# RADIOMASTER.net
KiCad netlist of a schematic drawn in Altium Designer
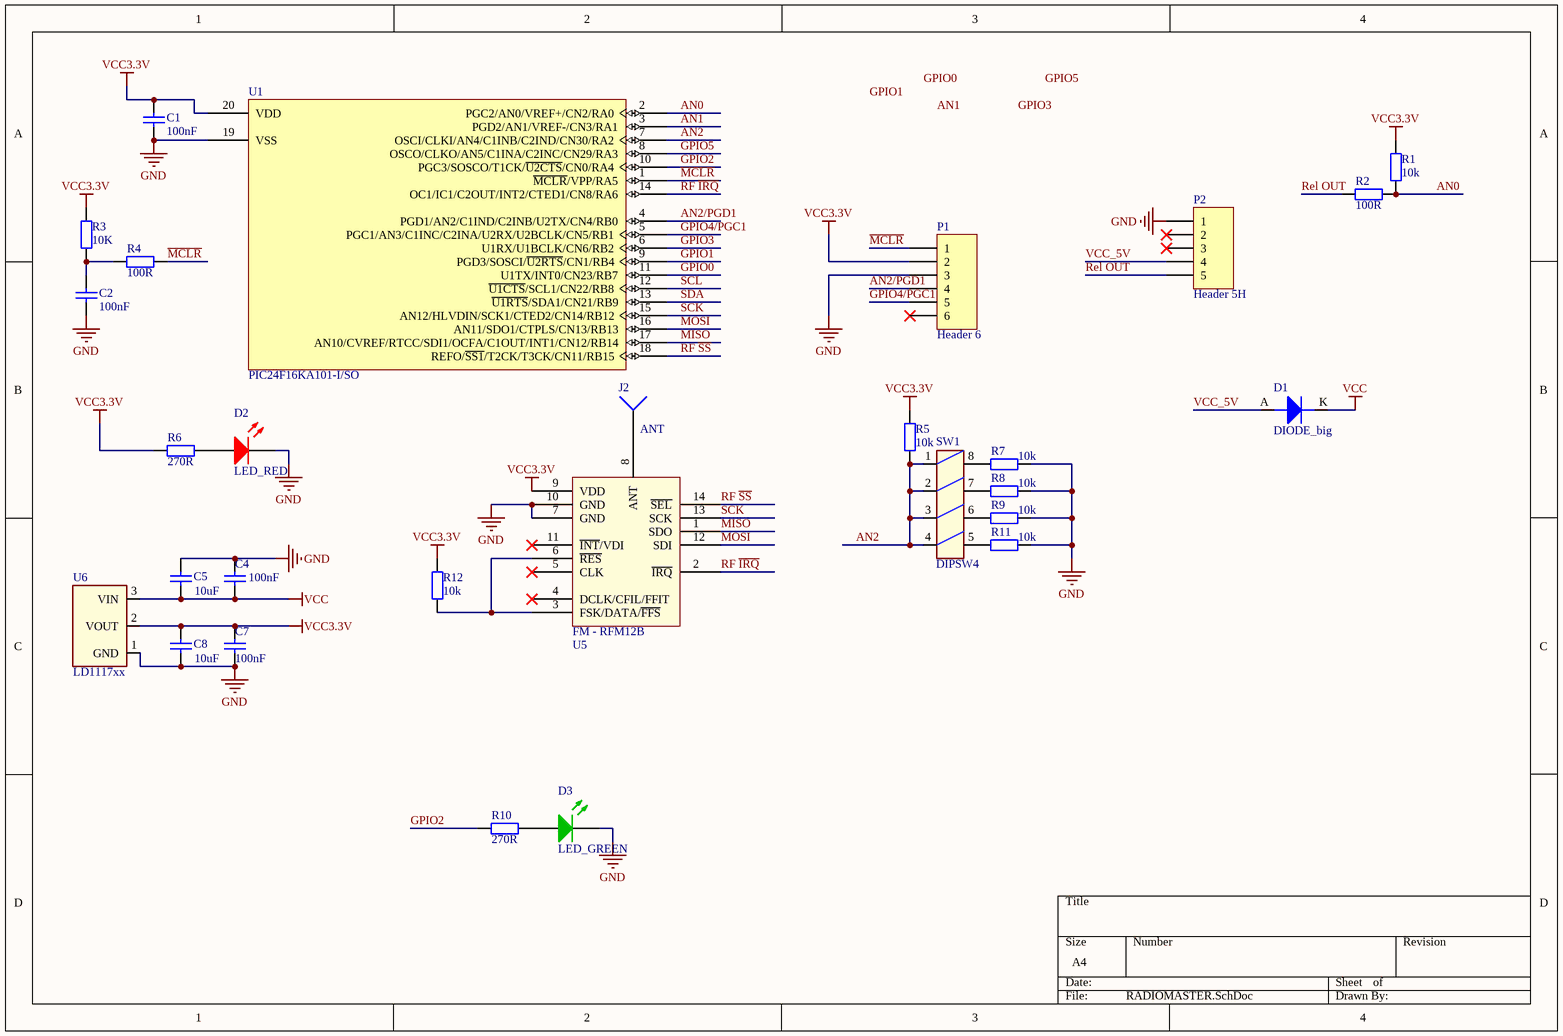
[diagram p0: RADIOMASTER.SchDoc]

(export (version "E")
  (design (tool "Eeschema 10.0.6"))
  (components
    (comp (ref "C1")
      (value "100nF")
      (footprint "FP_0805_CAP_060")
      (description "Capacitor")
      (fields (field (name "PUBLISHER") "Altium Limited"))
      (libsource (lib "Miscellaneous Devices") (part "Cap"))
    )
    (comp (ref "C2")
      (value "100nF")
      (footprint "FP_0805_CAP_060")
      (description "Capacitor")
      (fields (field (name "PUBLISHER") "Altium Limited"))
      (libsource (lib "Miscellaneous Devices") (part "Cap"))
    )
    (comp (ref "C4")
      (value "100nF")
      (footprint "FP_0603_CAP_080")
      (description "Capacitor")
      (fields (field (name "PUBLISHER") "Altium Limited"))
      (libsource (lib "Miscellaneous Devices") (part "Cap"))
    )
    (comp (ref "C5")
      (value "10uF")
      (footprint "FP_1206_CAP_085")
      (description "Capacitor")
      (fields (field (name "PUBLISHER") "Altium Limited"))
      (libsource (lib "Miscellaneous Devices") (part "Cap"))
    )
    (comp (ref "C7")
      (value "100nF")
      (footprint "FP_0603_CAP_080")
      (description "Capacitor")
      (fields (field (name "PUBLISHER") "Altium Limited"))
      (libsource (lib "Miscellaneous Devices") (part "Cap"))
    )
    (comp (ref "C8")
      (value "10uF")
      (footprint "FP_1206_CAP_085")
      (description "Capacitor")
      (fields (field (name "PUBLISHER") "Altium Limited"))
      (libsource (lib "Miscellaneous Devices") (part "Cap"))
    )
    (comp (ref "D1")
      (value "DIODE_big")
      (footprint "FP_SMA DO214AC")
      (libsource (lib "Diode") (part "DIODE_big"))
    )
    (comp (ref "D2")
      (value "LED_RED")
      (footprint "FP_0805_LED_RED")
      (description "Typical LED")
      (libsource (lib "Led_optical") (part "LED_R"))
    )
    (comp (ref "D3")
      (value "LED_GREEN")
      (footprint "FP_0805_LED_GREEN")
      (description "Typical LED")
      (libsource (lib "Led_optical") (part "LED_G"))
    )
    (comp (ref "J2")
      (value "ANT")
      (footprint "PIN1")
      (description "Socket")
      (fields (field (name "PUBLISHER") "Altium Limited"))
      (libsource (lib "Miscellaneous Connectors") (part "Socket"))
    )
    (comp (ref "P1")
      (value "Header 6")
      (footprint "HDR1X6")
      (description "Header, 6-Pin")
      (fields (field (name "PUBLISHER") "Altium Limited"))
      (libsource (lib "Miscellaneous Connectors") (part "Header 6"))
    )
    (comp (ref "P2")
      (value "Header 5H")
      (footprint "SORKAPOCS 5 P RM3.81 - no3d")
      (description "Header, 5-Pin, Right Angle")
      (fields (field (name "PUBLISHER") "Altium Limited"))
      (libsource (lib "Miscellaneous Connectors") (part "Header 5H"))
    )
    (comp (ref "R1")
      (value "10k")
      (footprint "FP_0805_RES")
      (description "Resistor")
      (fields (field (name "PUBLISHER") "Altium Limited"))
      (libsource (lib "") (part "Res3_1"))
    )
    (comp (ref "R2")
      (value "100R")
      (footprint "FP_0805_RES")
      (description "Resistor")
      (fields (field (name "PUBLISHER") "Altium Limited"))
      (libsource (lib "Miscellaneous Devices") (part "Res3"))
    )
    (comp (ref "R3")
      (value "10K")
      (footprint "FP_0805_RES")
      (description "Resistor")
      (fields (field (name "PUBLISHER") "Altium Limited"))
      (libsource (lib "") (part "Res3_1"))
    )
    (comp (ref "R4")
      (value "100R")
      (footprint "FP_0805_RES")
      (description "Resistor")
      (fields (field (name "PUBLISHER") "Altium Limited"))
      (libsource (lib "Miscellaneous Devices") (part "Res3"))
    )
    (comp (ref "R5")
      (value "10k")
      (footprint "FP_0805_RES")
      (description "Resistor")
      (fields (field (name "PUBLISHER") "Altium Limited"))
      (libsource (lib "") (part "Res3_1"))
    )
    (comp (ref "R6")
      (value "270R")
      (footprint "FP_0805_RES")
      (description "Resistor")
      (fields (field (name "PUBLISHER") "Altium Limited"))
      (libsource (lib "Miscellaneous Devices") (part "Res3"))
    )
    (comp (ref "R7")
      (value "10k")
      (footprint "FP_0805_RES")
      (description "Resistor")
      (fields (field (name "PUBLISHER") "Altium Limited"))
      (libsource (lib "Miscellaneous Devices") (part "Res3"))
    )
    (comp (ref "R8")
      (value "10k")
      (footprint "FP_0805_RES")
      (description "Resistor")
      (fields (field (name "PUBLISHER") "Altium Limited"))
      (libsource (lib "Miscellaneous Devices") (part "Res3"))
    )
    (comp (ref "R9")
      (value "10k")
      (footprint "FP_0805_RES")
      (description "Resistor")
      (fields (field (name "PUBLISHER") "Altium Limited"))
      (libsource (lib "Miscellaneous Devices") (part "Res3"))
    )
    (comp (ref "R10")
      (value "270R")
      (footprint "FP_0805_RES")
      (description "Resistor")
      (fields (field (name "PUBLISHER") "Altium Limited"))
      (libsource (lib "Miscellaneous Devices") (part "Res3"))
    )
    (comp (ref "R11")
      (value "10k")
      (footprint "FP_0805_RES")
      (description "Resistor")
      (fields (field (name "PUBLISHER") "Altium Limited"))
      (libsource (lib "Miscellaneous Devices") (part "Res3"))
    )
    (comp (ref "R12")
      (value "10k")
      (footprint "FP_0805_RES")
      (description "Resistor")
      (fields (field (name "PUBLISHER") "Altium Limited"))
      (libsource (lib "") (part "Res3_2"))
    )
    (comp (ref "SW1")
      (value "DIPSW4")
      (footprint "DIP switch 4 TH")
      (libsource (lib "Switch") (part "DIPSW4"))
    )
    (comp (ref "U1")
      (value "PIC24F16KA101-I/SO")
      (footprint "SOIC-SO20_N")
      (fields (field (name "PUBLISHER") "Altium Limited"))
      (libsource (lib "Microchip Microcontroller 16-Bit PIC24F") (part "PIC24F16KA101-I/SO"))
    )
    (comp (ref "U5")
      (value "RFM12B")
      (footprint "RFM12B-S1")
      (description "FM Module")
      (libsource (lib "EtherIOv2") (part "RFM12B"))
    )
    (comp (ref "U6")
      (value "LD1117xx")
      (footprint "SUPPLY_SOT223")
      (description "LD1117xx 3,3V lin reg")
      (libsource (lib "Supply") (part "LD1117xx"))
    )
  )
  (nets
    (net (code "1") (name "/AN0") (class "Default")
      (node (ref "R1") (pin "2") (pinfunction "2_2") (pintype "passive"))
      (node (ref "R2") (pin "1") (pinfunction "1_1") (pintype "passive"))
      (node (ref "U1") (pin "2") (pinfunction "PGC2/AN0/VREF+/CN2/RA0_2") (pintype "bidirectional"))
    )
    (net (code "2") (name "/AN1") (class "Default")
      (node (ref "U1") (pin "3") (pinfunction "PGD2/AN1/VREF-/CN3/RA1_3") (pintype "bidirectional"))
    )
    (net (code "3") (name "/AN2") (class "Default")
      (node (ref "R5") (pin "2") (pinfunction "2_2") (pintype "passive"))
      (node (ref "SW1") (pin "1") (pinfunction "1_1") (pintype "passive"))
      (node (ref "SW1") (pin "2") (pinfunction "2_2") (pintype "passive"))
      (node (ref "SW1") (pin "3") (pinfunction "3_3") (pintype "passive"))
      (node (ref "SW1") (pin "4") (pinfunction "4_4") (pintype "passive"))
      (node (ref "U1") (pin "7") (pinfunction "OSCI/CLKI/AN4/C1INB/C2IND/CN30/RA2_7") (pintype "bidirectional"))
    )
    (net (code "4") (name "/AN2{slash}PGD1") (class "Default")
      (node (ref "P1") (pin "4") (pinfunction "4_4") (pintype "passive"))
      (node (ref "U1") (pin "4") (pinfunction "PGD1/AN2/C1IND/C2INB/U2TX/CN4/RB0_4") (pintype "bidirectional"))
    )
    (net (code "5") (name "/GPIO0") (class "Default")
      (node (ref "U1") (pin "11") (pinfunction "U1TX/INT0/CN23/RB7_11") (pintype "bidirectional"))
    )
    (net (code "6") (name "/GPIO1") (class "Default")
      (node (ref "U1") (pin "9") (pinfunction "PGD3/SOSCI/~{U2RTS}/CN1/RB4_9") (pintype "bidirectional"))
    )
    (net (code "7") (name "/GPIO2") (class "Default")
      (node (ref "R10") (pin "2") (pinfunction "2_2") (pintype "passive"))
      (node (ref "U1") (pin "10") (pinfunction "PGC3/SOSCO/T1CK/~{U2CTS}/CN0/RA4_10") (pintype "bidirectional"))
    )
    (net (code "8") (name "/GPIO3") (class "Default")
      (node (ref "U1") (pin "6") (pinfunction "U1RX/U1BCLK/CN6/RB2_6") (pintype "bidirectional"))
    )
    (net (code "9") (name "/GPIO4{slash}PGC1") (class "Default")
      (node (ref "P1") (pin "5") (pinfunction "5_5") (pintype "passive"))
      (node (ref "U1") (pin "5") (pinfunction "PGC1/AN3/C1INC/C2INA/U2RX/U2BCLK/CN5/RB1_5") (pintype "bidirectional"))
    )
    (net (code "10") (name "/GPIO5") (class "Default")
      (node (ref "U1") (pin "8") (pinfunction "OSCO/CLKO/AN5/C1INA/C2INC/CN29/RA3_8") (pintype "bidirectional"))
    )
    (net (code "11") (name "/MISO") (class "Default")
      (node (ref "U1") (pin "17") (pinfunction "AN10/CVREF/RTCC/SDI1/OCFA/C1OUT/INT1/CN12/RB14_17") (pintype "bidirectional"))
      (node (ref "U5") (pin "1") (pinfunction "SDO_1") (pintype "passive"))
    )
    (net (code "12") (name "/MOSI") (class "Default")
      (node (ref "U1") (pin "16") (pinfunction "AN11/SDO1/CTPLS/CN13/RB13_16") (pintype "bidirectional"))
      (node (ref "U5") (pin "12") (pinfunction "SDI_12") (pintype "passive"))
    )
    (net (code "13") (name "/RF ~{IRQ}") (class "Default")
      (node (ref "U1") (pin "14") (pinfunction "OC1/IC1/C2OUT/INT2/CTED1/CN8/RA6_14") (pintype "bidirectional"))
      (node (ref "U5") (pin "2") (pinfunction "~{IRQ}_2") (pintype "passive"))
    )
    (net (code "14") (name "/RF ~{SS}") (class "Default")
      (node (ref "U1") (pin "18") (pinfunction "REFO/~{SS1}/T2CK/T3CK/CN11/RB15_18") (pintype "bidirectional"))
      (node (ref "U5") (pin "14") (pinfunction "~{SEL}_14") (pintype "passive"))
    )
    (net (code "15") (name "/Rel OUT") (class "Default")
      (node (ref "P2") (pin "5") (pinfunction "5_5") (pintype "passive"))
      (node (ref "R2") (pin "2") (pinfunction "2_2") (pintype "passive"))
    )
    (net (code "16") (name "/SCK") (class "Default")
      (node (ref "U1") (pin "15") (pinfunction "AN12/HLVDIN/SCK1/CTED2/CN14/RB12_15") (pintype "bidirectional"))
      (node (ref "U5") (pin "13") (pinfunction "SCK_13") (pintype "passive"))
    )
    (net (code "17") (name "/SCL") (class "Default")
      (node (ref "U1") (pin "12") (pinfunction "~{U1CTS}/SCL1/CN22/RB8_12") (pintype "bidirectional"))
    )
    (net (code "18") (name "/SDA") (class "Default")
      (node (ref "U1") (pin "13") (pinfunction "~{U1RTS}/SDA1/CN21/RB9_13") (pintype "bidirectional"))
    )
    (net (code "19") (name "/VCC_5V") (class "Default")
      (node (ref "D1") (pin "A") (pinfunction "A_A") (pintype "passive"))
      (node (ref "P2") (pin "4") (pinfunction "4_4") (pintype "passive"))
    )
    (net (code "20") (name "/~{MCLR}") (class "Default")
      (node (ref "P1") (pin "1") (pinfunction "1_1") (pintype "passive"))
      (node (ref "R4") (pin "1") (pinfunction "1_1") (pintype "passive"))
      (node (ref "U1") (pin "1") (pinfunction "~{MCLR}/VPP/RA5_1") (pintype "bidirectional"))
    )
    (net (code "21") (name "GND") (class "Default")
      (node (ref "C1") (pin "1") (pinfunction "1_1") (pintype "passive"))
      (node (ref "C2") (pin "1") (pinfunction "1_1") (pintype "passive"))
      (node (ref "C4") (pin "1") (pinfunction "1_1") (pintype "passive"))
      (node (ref "C5") (pin "2") (pinfunction "2_2") (pintype "passive"))
      (node (ref "C7") (pin "2") (pinfunction "2_2") (pintype "passive"))
      (node (ref "C8") (pin "1") (pinfunction "1_1") (pintype "passive"))
      (node (ref "D2") (pin "K") (pinfunction "K_K") (pintype "passive"))
      (node (ref "D3") (pin "K") (pinfunction "K_K") (pintype "passive"))
      (node (ref "P1") (pin "3") (pinfunction "3_3") (pintype "passive"))
      (node (ref "P2") (pin "1") (pinfunction "1_1") (pintype "passive"))
      (node (ref "R11") (pin "1") (pinfunction "1_1") (pintype "passive"))
      (node (ref "R7") (pin "1") (pinfunction "1_1") (pintype "passive"))
      (node (ref "R8") (pin "1") (pinfunction "1_1") (pintype "passive"))
      (node (ref "R9") (pin "1") (pinfunction "1_1") (pintype "passive"))
      (node (ref "U1") (pin "19") (pinfunction "VSS_19") (pintype "power_in"))
      (node (ref "U5") (pin "10") (pinfunction "GND_10") (pintype "passive"))
      (node (ref "U5") (pin "7") (pinfunction "GND_7") (pintype "passive"))
      (node (ref "U6") (pin "1") (pinfunction "GND_1") (pintype "passive"))
    )
    (net (code "22") (name "Net-(C2-Pad2)") (class "Default")
      (node (ref "C2") (pin "2") (pinfunction "2_2") (pintype "passive"))
      (node (ref "R3") (pin "2") (pinfunction "2_2") (pintype "passive"))
      (node (ref "R4") (pin "2") (pinfunction "2_2") (pintype "passive"))
    )
    (net (code "23") (name "Net-(D2-PadA)") (class "Default")
      (node (ref "D2") (pin "A") (pinfunction "A_A") (pintype "passive"))
      (node (ref "R6") (pin "1") (pinfunction "1_1") (pintype "passive"))
    )
    (net (code "24") (name "Net-(D3-PadA)") (class "Default")
      (node (ref "D3") (pin "A") (pinfunction "A_A") (pintype "passive"))
      (node (ref "R10") (pin "1") (pinfunction "1_1") (pintype "passive"))
    )
    (net (code "25") (name "Net-(R7-Pad2)") (class "Default")
      (node (ref "R7") (pin "2") (pinfunction "2_2") (pintype "passive"))
      (node (ref "SW1") (pin "8") (pinfunction "8_8") (pintype "passive"))
    )
    (net (code "26") (name "Net-(R8-Pad2)") (class "Default")
      (node (ref "R8") (pin "2") (pinfunction "2_2") (pintype "passive"))
      (node (ref "SW1") (pin "7") (pinfunction "7_7") (pintype "passive"))
    )
    (net (code "27") (name "Net-(R9-Pad2)") (class "Default")
      (node (ref "R9") (pin "2") (pinfunction "2_2") (pintype "passive"))
      (node (ref "SW1") (pin "6") (pinfunction "6_6") (pintype "passive"))
    )
    (net (code "28") (name "Net-(R11-Pad2)") (class "Default")
      (node (ref "R11") (pin "2") (pinfunction "2_2") (pintype "passive"))
      (node (ref "SW1") (pin "5") (pinfunction "5_5") (pintype "passive"))
    )
    (net (code "29") (name "Net-(U5-ANT)") (class "Default")
      (node (ref "J2") (pin "1") (pinfunction "1_1") (pintype "passive"))
      (node (ref "U5") (pin "8") (pinfunction "ANT_8") (pintype "passive"))
    )
    (net (code "30") (name "Net-(U5-FSK{slash}DATA{slash}~{FFS})") (class "Default")
      (node (ref "R12") (pin "1") (pinfunction "1_1") (pintype "passive"))
      (node (ref "U5") (pin "3") (pinfunction "FSK/DATA/~{FFS}_3") (pintype "passive"))
      (node (ref "U5") (pin "6") (pinfunction "~{RES}_6") (pintype "passive"))
    )
    (net (code "31") (name "VCC") (class "Default")
      (node (ref "C4") (pin "2") (pinfunction "2_2") (pintype "passive"))
      (node (ref "C5") (pin "1") (pinfunction "1_1") (pintype "passive"))
      (node (ref "D1") (pin "K") (pinfunction "K_K") (pintype "passive"))
      (node (ref "U6") (pin "3") (pinfunction "VIN_3") (pintype "passive"))
    )
    (net (code "32") (name "VCC3.3V") (class "Default")
      (node (ref "C1") (pin "2") (pinfunction "2_2") (pintype "passive"))
      (node (ref "C7") (pin "1") (pinfunction "1_1") (pintype "passive"))
      (node (ref "C8") (pin "2") (pinfunction "2_2") (pintype "passive"))
      (node (ref "P1") (pin "2") (pinfunction "2_2") (pintype "passive"))
      (node (ref "R1") (pin "1") (pinfunction "1_1") (pintype "passive"))
      (node (ref "R12") (pin "2") (pinfunction "2_2") (pintype "passive"))
      (node (ref "R3") (pin "1") (pinfunction "1_1") (pintype "passive"))
      (node (ref "R5") (pin "1") (pinfunction "1_1") (pintype "passive"))
      (node (ref "R6") (pin "2") (pinfunction "2_2") (pintype "passive"))
      (node (ref "U1") (pin "20") (pinfunction "VDD_20") (pintype "power_in"))
      (node (ref "U5") (pin "9") (pinfunction "VDD_9") (pintype "passive"))
      (node (ref "U6") (pin "2") (pinfunction "VOUT_2") (pintype "passive"))
    )
    (net (code "33") (name "unconnected-(P1-Pad6)") (class "Default")
      (node (ref "P1") (pin "6") (pinfunction "6_6") (pintype "passive+no_connect"))
    )
    (net (code "34") (name "unconnected-(P2-Pad2)") (class "Default")
      (node (ref "P2") (pin "2") (pinfunction "2_2") (pintype "passive+no_connect"))
    )
    (net (code "35") (name "unconnected-(P2-Pad3)") (class "Default")
      (node (ref "P2") (pin "3") (pinfunction "3_3") (pintype "passive+no_connect"))
    )
    (net (code "36") (name "unconnected-(U5-CLK-Pad5)") (class "Default")
      (node (ref "U5") (pin "5") (pinfunction "CLK_5") (pintype "passive+no_connect"))
    )
    (net (code "37") (name "unconnected-(U5-DCLK{slash}CFIL{slash}FFIT-Pad4)") (class "Default")
      (node (ref "U5") (pin "4") (pinfunction "DCLK/CFIL/FFIT_4") (pintype "passive+no_connect"))
    )
    (net (code "38") (name "unconnected-(U5-~{INT}{slash}VDI-Pad11)") (class "Default")
      (node (ref "U5") (pin "11") (pinfunction "~{INT}/VDI_11") (pintype "passive+no_connect"))
    )
  )
)
